# MCU_Radios_and_Sensors.net
KiCad netlist of a schematic drawn in Altium Designer
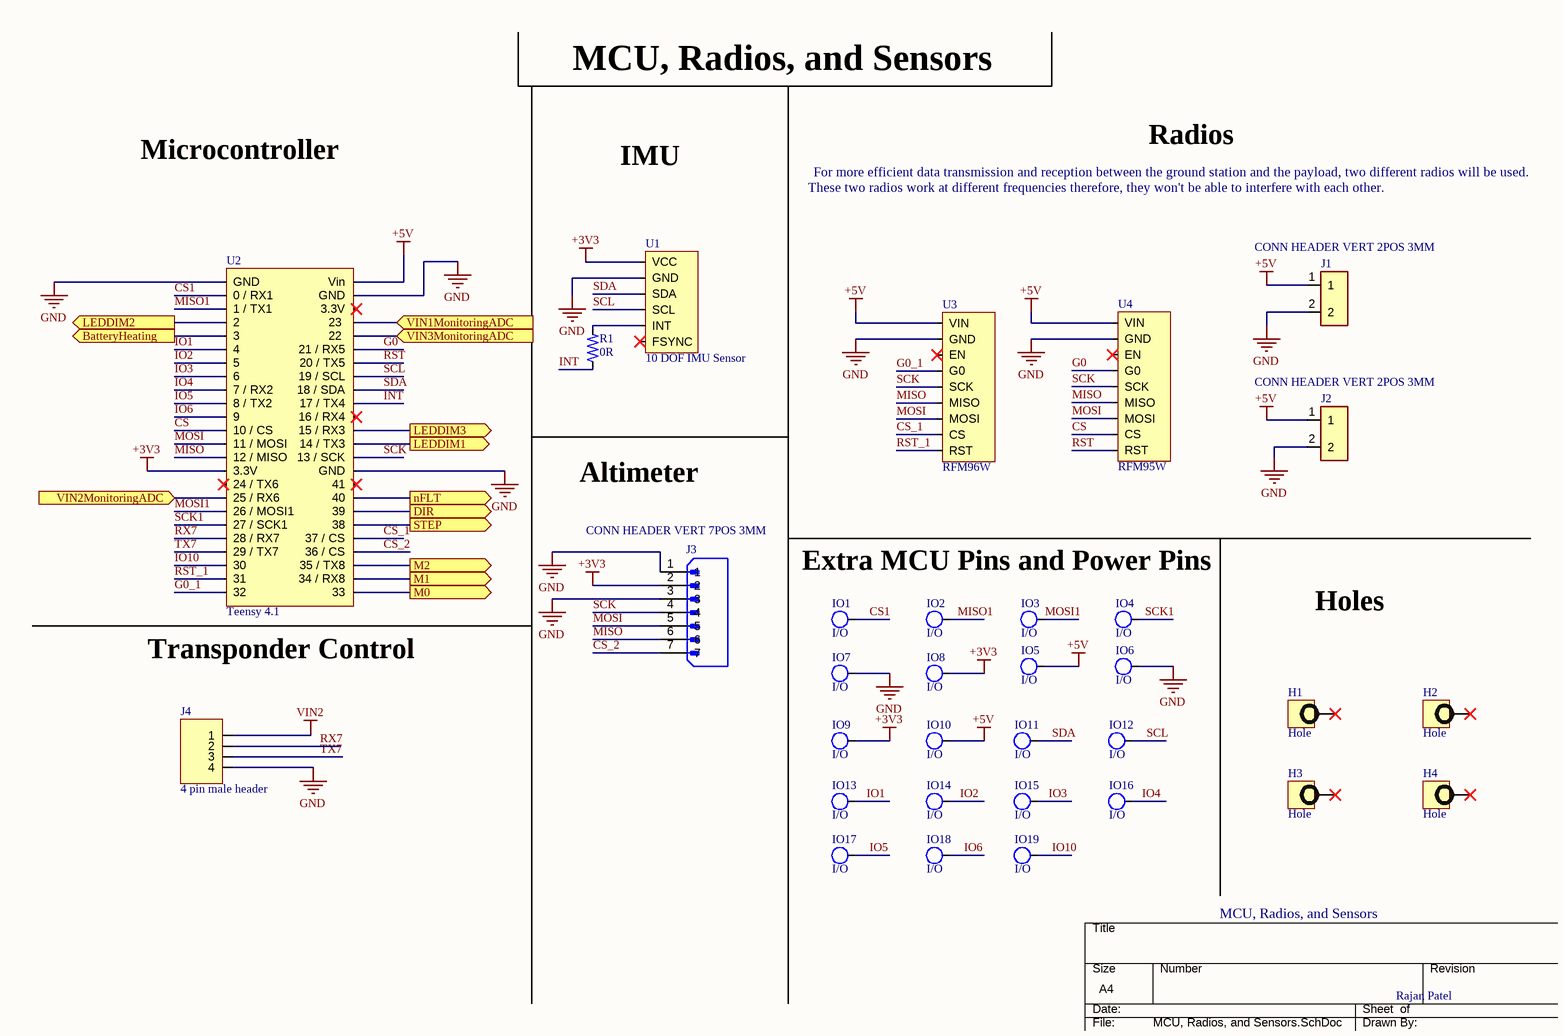
[diagram p0: MCU, Radios, and Sensors.SchDoc]

(export (version "E")
  (design (tool "Eeschema 10.0.6"))
  (components
    (comp (ref "H1") (value "Hole") (footprint "M3 Holes") (libsource (lib "MRT SCH Library") (part "Hole")))
    (comp (ref "H2") (value "Hole") (footprint "M3 Holes") (libsource (lib "MRT SCH Library") (part "Hole")))
    (comp (ref "H3") (value "Hole") (footprint "M3 Holes") (libsource (lib "MRT SCH Library") (part "Hole")))
    (comp (ref "H4") (value "Hole") (footprint "M3 Holes") (libsource (lib "MRT SCH Library") (part "Hole")))
    (comp (ref "IO1") (value "I/O") (footprint "Pins") (libsource (lib "Payload schlib") (part "I/O")))
    (comp (ref "IO2") (value "I/O") (footprint "Pins") (libsource (lib "Payload schlib") (part "I/O")))
    (comp (ref "IO3") (value "I/O") (footprint "Pins") (libsource (lib "Payload schlib") (part "I/O")))
    (comp (ref "IO4") (value "I/O") (footprint "Pins") (libsource (lib "Payload schlib") (part "I/O")))
    (comp (ref "IO5") (value "I/O") (footprint "Pins") (libsource (lib "Payload schlib") (part "I/O")))
    (comp (ref "IO6") (value "I/O") (footprint "Pins") (libsource (lib "Payload schlib") (part "I/O")))
    (comp (ref "IO7") (value "I/O") (footprint "Pins") (libsource (lib "Payload schlib") (part "I/O")))
    (comp (ref "IO8") (value "I/O") (footprint "Pins") (libsource (lib "Payload schlib") (part "I/O")))
    (comp (ref "IO9") (value "I/O") (footprint "Pins") (libsource (lib "Payload schlib") (part "I/O")))
    (comp (ref "IO10") (value "I/O") (footprint "Pins") (libsource (lib "Payload schlib") (part "I/O")))
    (comp (ref "IO11") (value "I/O") (footprint "Pins") (libsource (lib "Payload schlib") (part "I/O")))
    (comp (ref "IO12") (value "I/O") (footprint "Pins") (libsource (lib "Payload schlib") (part "I/O")))
    (comp (ref "IO13") (value "I/O") (footprint "Pins") (libsource (lib "Payload schlib") (part "I/O")))
    (comp (ref "IO14") (value "I/O") (footprint "Pins") (libsource (lib "Payload schlib") (part "I/O")))
    (comp (ref "IO15") (value "I/O") (footprint "Pins") (libsource (lib "Payload schlib") (part "I/O")))
    (comp (ref "IO16") (value "I/O") (footprint "Pins") (libsource (lib "Payload schlib") (part "I/O")))
    (comp (ref "IO17") (value "I/O") (footprint "Pins") (libsource (lib "Payload schlib") (part "I/O")))
    (comp (ref "IO18") (value "I/O") (footprint "Pins") (libsource (lib "Payload schlib") (part "I/O")))
    (comp (ref "IO19") (value "I/O") (footprint "Pins") (libsource (lib "Payload schlib") (part "I/O")))
    (comp (ref "J1")
      (value "CONN HEADER VERT 2POS 3MM")
      (footprint "CONN HEADER VERT 2POS 3MM")
      (description "Rectangular Power Connector, 2 Contact(s), Female, Solder Terminal")
      (fields (field (name "MF") "Molex") (field (name "MP") "0436500200"))
      (libsource (lib "Payload schlib") (part "0436500228"))
    )
    (comp (ref "J2")
      (value "CONN HEADER VERT 2POS 3MM")
      (footprint "CONN HEADER VERT 2POS 3MM")
      (description "Rectangular Power Connector, 2 Contact(s), Female, Solder Terminal")
      (fields (field (name "MF") "Molex") (field (name "MP") "0436500200"))
      (libsource (lib "Payload schlib") (part "0436500228"))
    )
    (comp (ref "J3")
      (value "CONN HEADER VERT 7POS 3MM")
      (footprint "MOLEX_436500728")
      (description "Connector Header Through Hole 7 position 0.118 (3.00mm)")
      (fields (field (name "MF") "Molex") (field (name "MP") "436500728"))
      (libsource (lib "Payload schlib") (part "436500728"))
    )
    (comp (ref "J4")
      (value "4 pin male header")
      (footprint "4 Pin Male Header")
      (libsource (lib "Payload schlib") (part "4 pin male header"))
    )
    (comp (ref "R1")
      (value "0R")
      (footprint "res 0805")
      (fields
        (field (name "MP") "2-2176053-2")
        (field (name "MF") "TE Connectivity")
        (field (name "TOLERANCE") "1%")
      )
      (libsource (lib "Payload schlib") (part "Resistor 0805"))
    )
    (comp (ref "U1")
      (value "10 DOF IMU Sensor")
      (footprint "10 DOF IMU Sensor")
      (description "10 DOF IMU Sensor, ICM20948 Onboard, Low Power, High Precision")
      (libsource (lib "Payload schlib") (part "10 DOF IMU Sensor"))
    )
    (comp (ref "U2")
      (value "Teensy 4.1")
      (footprint "Teensy 4.1")
      (description "iMXRT1062 Microcontroller Development Board 600MHz CPU 1GB RAM 8MB Flash")
      (fields (field (name "MANUFACTURER") "SparkFun") (field (name "MANUFACTURER PART NUMBER") "DEV-16771"))
      (libsource (lib "Payload schlib") (part "Teensy 4.1"))
    )
    (comp (ref "U3")
      (value "RFM96W")
      (footprint "RFM95W")
      (description "Banana Plug; Female to Multi-Stacking Banana Plug; Nickel Plated Brass")
      (fields
        (field (name "MANUFACTURER") "Adafruit Industries")
        (field (name "MANUFACTURER PART NUMBER") "3072")
      )
      (libsource (lib "Payload schlib") (part "RFM96W"))
    )
    (comp (ref "U4")
      (value "RFM95W")
      (footprint "RFM95W")
      (description "Adafruit RFM95W LoRa Radio Transceiver Breakout - 868 or 915 MHz")
      (fields
        (field (name "MANUFACTURER") "Adafruit Industries")
        (field (name "MANUFACTURER PART NUMBER") "3072")
      )
      (libsource (lib "Payload schlib") (part "RFM95W"))
    )
  )
  (nets
    (net (code "1") (name "+3V3") (class "Default")
      (node (ref "IO8") (pin "1") (pinfunction "1_1") (pintype "passive"))
      (node (ref "IO9") (pin "1") (pinfunction "1_1") (pintype "passive"))
      (node (ref "J3") (pin "2") (pinfunction "2_2") (pintype "passive"))
      (node (ref "U1") (pin "1") (pinfunction "VCC_1") (pintype "passive"))
      (node (ref "U2") (pin "15") (pinfunction "3.3V_15") (pintype "passive"))
    )
    (net (code "2") (name "+5V") (class "Default")
      (node (ref "IO10") (pin "1") (pinfunction "1_1") (pintype "passive"))
      (node (ref "IO5") (pin "1") (pinfunction "1_1") (pintype "passive"))
      (node (ref "J1") (pin "1") (pinfunction "1_1") (pintype "passive"))
      (node (ref "J2") (pin "1") (pinfunction "1_1") (pintype "passive"))
      (node (ref "U2") (pin "48") (pinfunction "Vin_48") (pintype "passive"))
      (node (ref "U3") (pin "1") (pinfunction "VIN_1") (pintype "passive"))
      (node (ref "U4") (pin "1") (pinfunction "VIN_1") (pintype "passive"))
    )
    (net (code "3") (name "/BatteryHeating") (class "Default")
      (node (ref "U2") (pin "5") (pinfunction "3_5") (pintype "passive"))
    )
    (net (code "4") (name "/CS") (class "Default")
      (node (ref "U2") (pin "12") (pinfunction "10_/_CS_12") (pintype "passive"))
      (node (ref "U4") (pin "8") (pinfunction "CS_8") (pintype "passive"))
    )
    (net (code "5") (name "/CS1") (class "Default")
      (node (ref "IO1") (pin "1") (pinfunction "1_1") (pintype "passive"))
      (node (ref "U2") (pin "2") (pinfunction "0_/_RX1_2") (pintype "passive"))
    )
    (net (code "6") (name "/CS_1") (class "Default")
      (node (ref "U2") (pin "29") (pinfunction "37_/_CS_29") (pintype "passive"))
      (node (ref "U3") (pin "8") (pinfunction "CS_8") (pintype "passive"))
    )
    (net (code "7") (name "/CS_2") (class "Default")
      (node (ref "J3") (pin "7") (pinfunction "7_7") (pintype "passive"))
      (node (ref "U2") (pin "28") (pinfunction "36_/_CS_28") (pintype "passive"))
    )
    (net (code "8") (name "/DIR") (class "Default")
      (node (ref "U2") (pin "31") (pinfunction "39_31") (pintype "passive"))
    )
    (net (code "9") (name "/G0") (class "Default")
      (node (ref "U2") (pin "43") (pinfunction "21_/_RX5_43") (pintype "passive"))
      (node (ref "U4") (pin "4") (pinfunction "G0_4") (pintype "passive"))
    )
    (net (code "10") (name "/G0_1") (class "Default")
      (node (ref "U2") (pin "24") (pinfunction "32_24") (pintype "passive"))
      (node (ref "U3") (pin "4") (pinfunction "G0_4") (pintype "passive"))
    )
    (net (code "11") (name "/INT") (class "Default")
      (node (ref "R1") (pin "1") (pinfunction "1_1") (pintype "passive"))
      (node (ref "U2") (pin "39") (pinfunction "17_/_TX4_39") (pintype "passive"))
    )
    (net (code "12") (name "/IO1") (class "Default")
      (node (ref "IO13") (pin "1") (pinfunction "1_1") (pintype "passive"))
      (node (ref "U2") (pin "6") (pinfunction "4_6") (pintype "passive"))
    )
    (net (code "13") (name "/IO2") (class "Default")
      (node (ref "IO14") (pin "1") (pinfunction "1_1") (pintype "passive"))
      (node (ref "U2") (pin "7") (pinfunction "5_7") (pintype "passive"))
    )
    (net (code "14") (name "/IO3") (class "Default")
      (node (ref "IO15") (pin "1") (pinfunction "1_1") (pintype "passive"))
      (node (ref "U2") (pin "8") (pinfunction "6_8") (pintype "passive"))
    )
    (net (code "15") (name "/IO4") (class "Default")
      (node (ref "IO16") (pin "1") (pinfunction "1_1") (pintype "passive"))
      (node (ref "U2") (pin "9") (pinfunction "7_/_RX2_9") (pintype "passive"))
    )
    (net (code "16") (name "/IO5") (class "Default")
      (node (ref "IO17") (pin "1") (pinfunction "1_1") (pintype "passive"))
      (node (ref "U2") (pin "10") (pinfunction "8_/_TX2_10") (pintype "passive"))
    )
    (net (code "17") (name "/IO6") (class "Default")
      (node (ref "IO18") (pin "1") (pinfunction "1_1") (pintype "passive"))
      (node (ref "U2") (pin "11") (pinfunction "9_11") (pintype "passive"))
    )
    (net (code "18") (name "/IO10") (class "Default")
      (node (ref "IO19") (pin "1") (pinfunction "1_1") (pintype "passive"))
      (node (ref "U2") (pin "22") (pinfunction "30_22") (pintype "passive"))
    )
    (net (code "19") (name "/LEDDIM1") (class "Default")
      (node (ref "U2") (pin "36") (pinfunction "14_/_TX3_36") (pintype "passive"))
    )
    (net (code "20") (name "/LEDDIM2") (class "Default")
      (node (ref "U2") (pin "4") (pinfunction "2_4") (pintype "passive"))
    )
    (net (code "21") (name "/LEDDIM3") (class "Default")
      (node (ref "U2") (pin "37") (pinfunction "15_/_RX3_37") (pintype "passive"))
    )
    (net (code "22") (name "/M0") (class "Default")
      (node (ref "U2") (pin "25") (pinfunction "33_25") (pintype "passive"))
    )
    (net (code "23") (name "/M1") (class "Default")
      (node (ref "U2") (pin "26") (pinfunction "34_/_RX8_26") (pintype "passive"))
    )
    (net (code "24") (name "/M2") (class "Default")
      (node (ref "U2") (pin "27") (pinfunction "35_/_TX8_27") (pintype "passive"))
    )
    (net (code "25") (name "/MISO") (class "Default")
      (node (ref "J3") (pin "6") (pinfunction "6_6") (pintype "passive"))
      (node (ref "U2") (pin "14") (pinfunction "12_/_MISO_14") (pintype "passive"))
      (node (ref "U3") (pin "6") (pinfunction "MISO_6") (pintype "passive"))
      (node (ref "U4") (pin "6") (pinfunction "MISO_6") (pintype "passive"))
    )
    (net (code "26") (name "/MISO1") (class "Default")
      (node (ref "IO2") (pin "1") (pinfunction "1_1") (pintype "passive"))
      (node (ref "U2") (pin "3") (pinfunction "1_/_TX1_3") (pintype "passive"))
    )
    (net (code "27") (name "/MOSI") (class "Default")
      (node (ref "J3") (pin "5") (pinfunction "5_5") (pintype "passive"))
      (node (ref "U2") (pin "13") (pinfunction "11_/_MOSI_13") (pintype "passive"))
      (node (ref "U3") (pin "7") (pinfunction "MOSI_7") (pintype "passive"))
      (node (ref "U4") (pin "7") (pinfunction "MOSI_7") (pintype "passive"))
    )
    (net (code "28") (name "/MOSI1") (class "Default")
      (node (ref "IO3") (pin "1") (pinfunction "1_1") (pintype "passive"))
      (node (ref "U2") (pin "18") (pinfunction "26_/_MOSI1_18") (pintype "passive"))
    )
    (net (code "29") (name "/RST") (class "Default")
      (node (ref "U2") (pin "42") (pinfunction "20_/_TX5_42") (pintype "passive"))
      (node (ref "U4") (pin "9") (pinfunction "RST_9") (pintype "passive"))
    )
    (net (code "30") (name "/RST_1") (class "Default")
      (node (ref "U2") (pin "23") (pinfunction "31_23") (pintype "passive"))
      (node (ref "U3") (pin "9") (pinfunction "RST_9") (pintype "passive"))
    )
    (net (code "31") (name "/RX7") (class "Default")
      (node (ref "J4") (pin "2") (pinfunction "2_2") (pintype "passive"))
      (node (ref "U2") (pin "20") (pinfunction "28_/_RX7_20") (pintype "passive"))
    )
    (net (code "32") (name "/SCK") (class "Default")
      (node (ref "J3") (pin "4") (pinfunction "4_4") (pintype "passive"))
      (node (ref "U2") (pin "35") (pinfunction "13_/_SCK_35") (pintype "passive"))
      (node (ref "U3") (pin "5") (pinfunction "SCK_5") (pintype "passive"))
      (node (ref "U4") (pin "5") (pinfunction "SCK_5") (pintype "passive"))
    )
    (net (code "33") (name "/SCK1") (class "Default")
      (node (ref "IO4") (pin "1") (pinfunction "1_1") (pintype "passive"))
      (node (ref "U2") (pin "19") (pinfunction "27_/_SCK1_19") (pintype "passive"))
    )
    (net (code "34") (name "/SCL") (class "Default")
      (node (ref "IO12") (pin "1") (pinfunction "1_1") (pintype "passive"))
      (node (ref "U1") (pin "4") (pinfunction "SCL_4") (pintype "passive"))
      (node (ref "U2") (pin "41") (pinfunction "19_/_SCL_41") (pintype "passive"))
    )
    (net (code "35") (name "/SDA") (class "Default")
      (node (ref "IO11") (pin "1") (pinfunction "1_1") (pintype "passive"))
      (node (ref "U1") (pin "3") (pinfunction "SDA_3") (pintype "passive"))
      (node (ref "U2") (pin "40") (pinfunction "18_/_SDA_40") (pintype "passive"))
    )
    (net (code "36") (name "/STEP") (class "Default")
      (node (ref "U2") (pin "30") (pinfunction "38_30") (pintype "passive"))
    )
    (net (code "37") (name "/TX7") (class "Default")
      (node (ref "J4") (pin "3") (pinfunction "3_3") (pintype "passive"))
      (node (ref "U2") (pin "21") (pinfunction "29_/_TX7_21") (pintype "passive"))
    )
    (net (code "38") (name "/VIN1MonitoringADC") (class "Default")
      (node (ref "U2") (pin "45") (pinfunction "23_45") (pintype "passive"))
    )
    (net (code "39") (name "/VIN2MonitoringADC") (class "Default")
      (node (ref "U2") (pin "17") (pinfunction "25_/_RX6_17") (pintype "passive"))
    )
    (net (code "40") (name "/VIN3MonitoringADC") (class "Default")
      (node (ref "U2") (pin "44") (pinfunction "22_44") (pintype "passive"))
    )
    (net (code "41") (name "/nFLT") (class "Default")
      (node (ref "U2") (pin "32") (pinfunction "40_32") (pintype "passive"))
    )
    (net (code "42") (name "GND") (class "Default")
      (node (ref "IO6") (pin "1") (pinfunction "1_1") (pintype "passive"))
      (node (ref "IO7") (pin "1") (pinfunction "1_1") (pintype "passive"))
      (node (ref "J1") (pin "2") (pinfunction "2_2") (pintype "passive"))
      (node (ref "J2") (pin "2") (pinfunction "2_2") (pintype "passive"))
      (node (ref "J3") (pin "1") (pinfunction "1_1") (pintype "passive"))
      (node (ref "J3") (pin "3") (pinfunction "3_3") (pintype "passive"))
      (node (ref "J4") (pin "4") (pinfunction "4_4") (pintype "passive"))
      (node (ref "U1") (pin "2") (pinfunction "GND_2") (pintype "passive"))
      (node (ref "U2") (pin "1") (pinfunction "GND_1") (pintype "passive"))
      (node (ref "U2") (pin "34") (pinfunction "GND_34") (pintype "passive"))
      (node (ref "U2") (pin "47") (pinfunction "GND_47") (pintype "passive"))
      (node (ref "U3") (pin "2") (pinfunction "GND_2") (pintype "passive"))
      (node (ref "U4") (pin "2") (pinfunction "GND_2") (pintype "passive"))
    )
    (net (code "43") (name "Net-(U1-INT)") (class "Default")
      (node (ref "R1") (pin "2") (pinfunction "2_2") (pintype "passive"))
      (node (ref "U1") (pin "5") (pinfunction "INT_5") (pintype "passive"))
    )
    (net (code "44") (name "VIN2") (class "Default")
      (node (ref "J4") (pin "1") (pinfunction "1_1") (pintype "passive"))
    )
    (net (code "45") (name "unconnected-(H1-TERMINAL-Pad1)") (class "Default")
      (node (ref "H1") (pin "1") (pinfunction "TERMINAL_1") (pintype "passive+no_connect"))
    )
    (net (code "46") (name "unconnected-(H2-TERMINAL-Pad1)") (class "Default")
      (node (ref "H2") (pin "1") (pinfunction "TERMINAL_1") (pintype "passive+no_connect"))
    )
    (net (code "47") (name "unconnected-(H3-TERMINAL-Pad1)") (class "Default")
      (node (ref "H3") (pin "1") (pinfunction "TERMINAL_1") (pintype "passive+no_connect"))
    )
    (net (code "48") (name "unconnected-(H4-TERMINAL-Pad1)") (class "Default")
      (node (ref "H4") (pin "1") (pinfunction "TERMINAL_1") (pintype "passive+no_connect"))
    )
    (net (code "49") (name "unconnected-(U1-FSYNC-Pad6)") (class "Default")
      (node (ref "U1") (pin "6") (pinfunction "FSYNC_6") (pintype "passive+no_connect"))
    )
    (net (code "50") (name "unconnected-(U2-3.3V-Pad46)") (class "Default")
      (node (ref "U2") (pin "46") (pinfunction "3.3V_46") (pintype "passive+no_connect"))
    )
    (net (code "51") (name "unconnected-(U2-16_{slash}_RX4-Pad38)") (class "Default")
      (node (ref "U2") (pin "38") (pinfunction "16_/_RX4_38") (pintype "passive+no_connect"))
    )
    (net (code "52") (name "unconnected-(U2-24_{slash}_TX6-Pad16)") (class "Default")
      (node (ref "U2") (pin "16") (pinfunction "24_/_TX6_16") (pintype "passive+no_connect"))
    )
    (net (code "53") (name "unconnected-(U2-41-Pad33)") (class "Default")
      (node (ref "U2") (pin "33") (pinfunction "41_33") (pintype "passive+no_connect"))
    )
    (net (code "54") (name "unconnected-(U3-EN-Pad3)") (class "Default")
      (node (ref "U3") (pin "3") (pinfunction "EN_3") (pintype "passive+no_connect"))
    )
    (net (code "55") (name "unconnected-(U4-EN-Pad3)") (class "Default")
      (node (ref "U4") (pin "3") (pinfunction "EN_3") (pintype "passive+no_connect"))
    )
  )
)
